# Microcontroller.net
KiCad netlist of a schematic drawn in Altium Designer
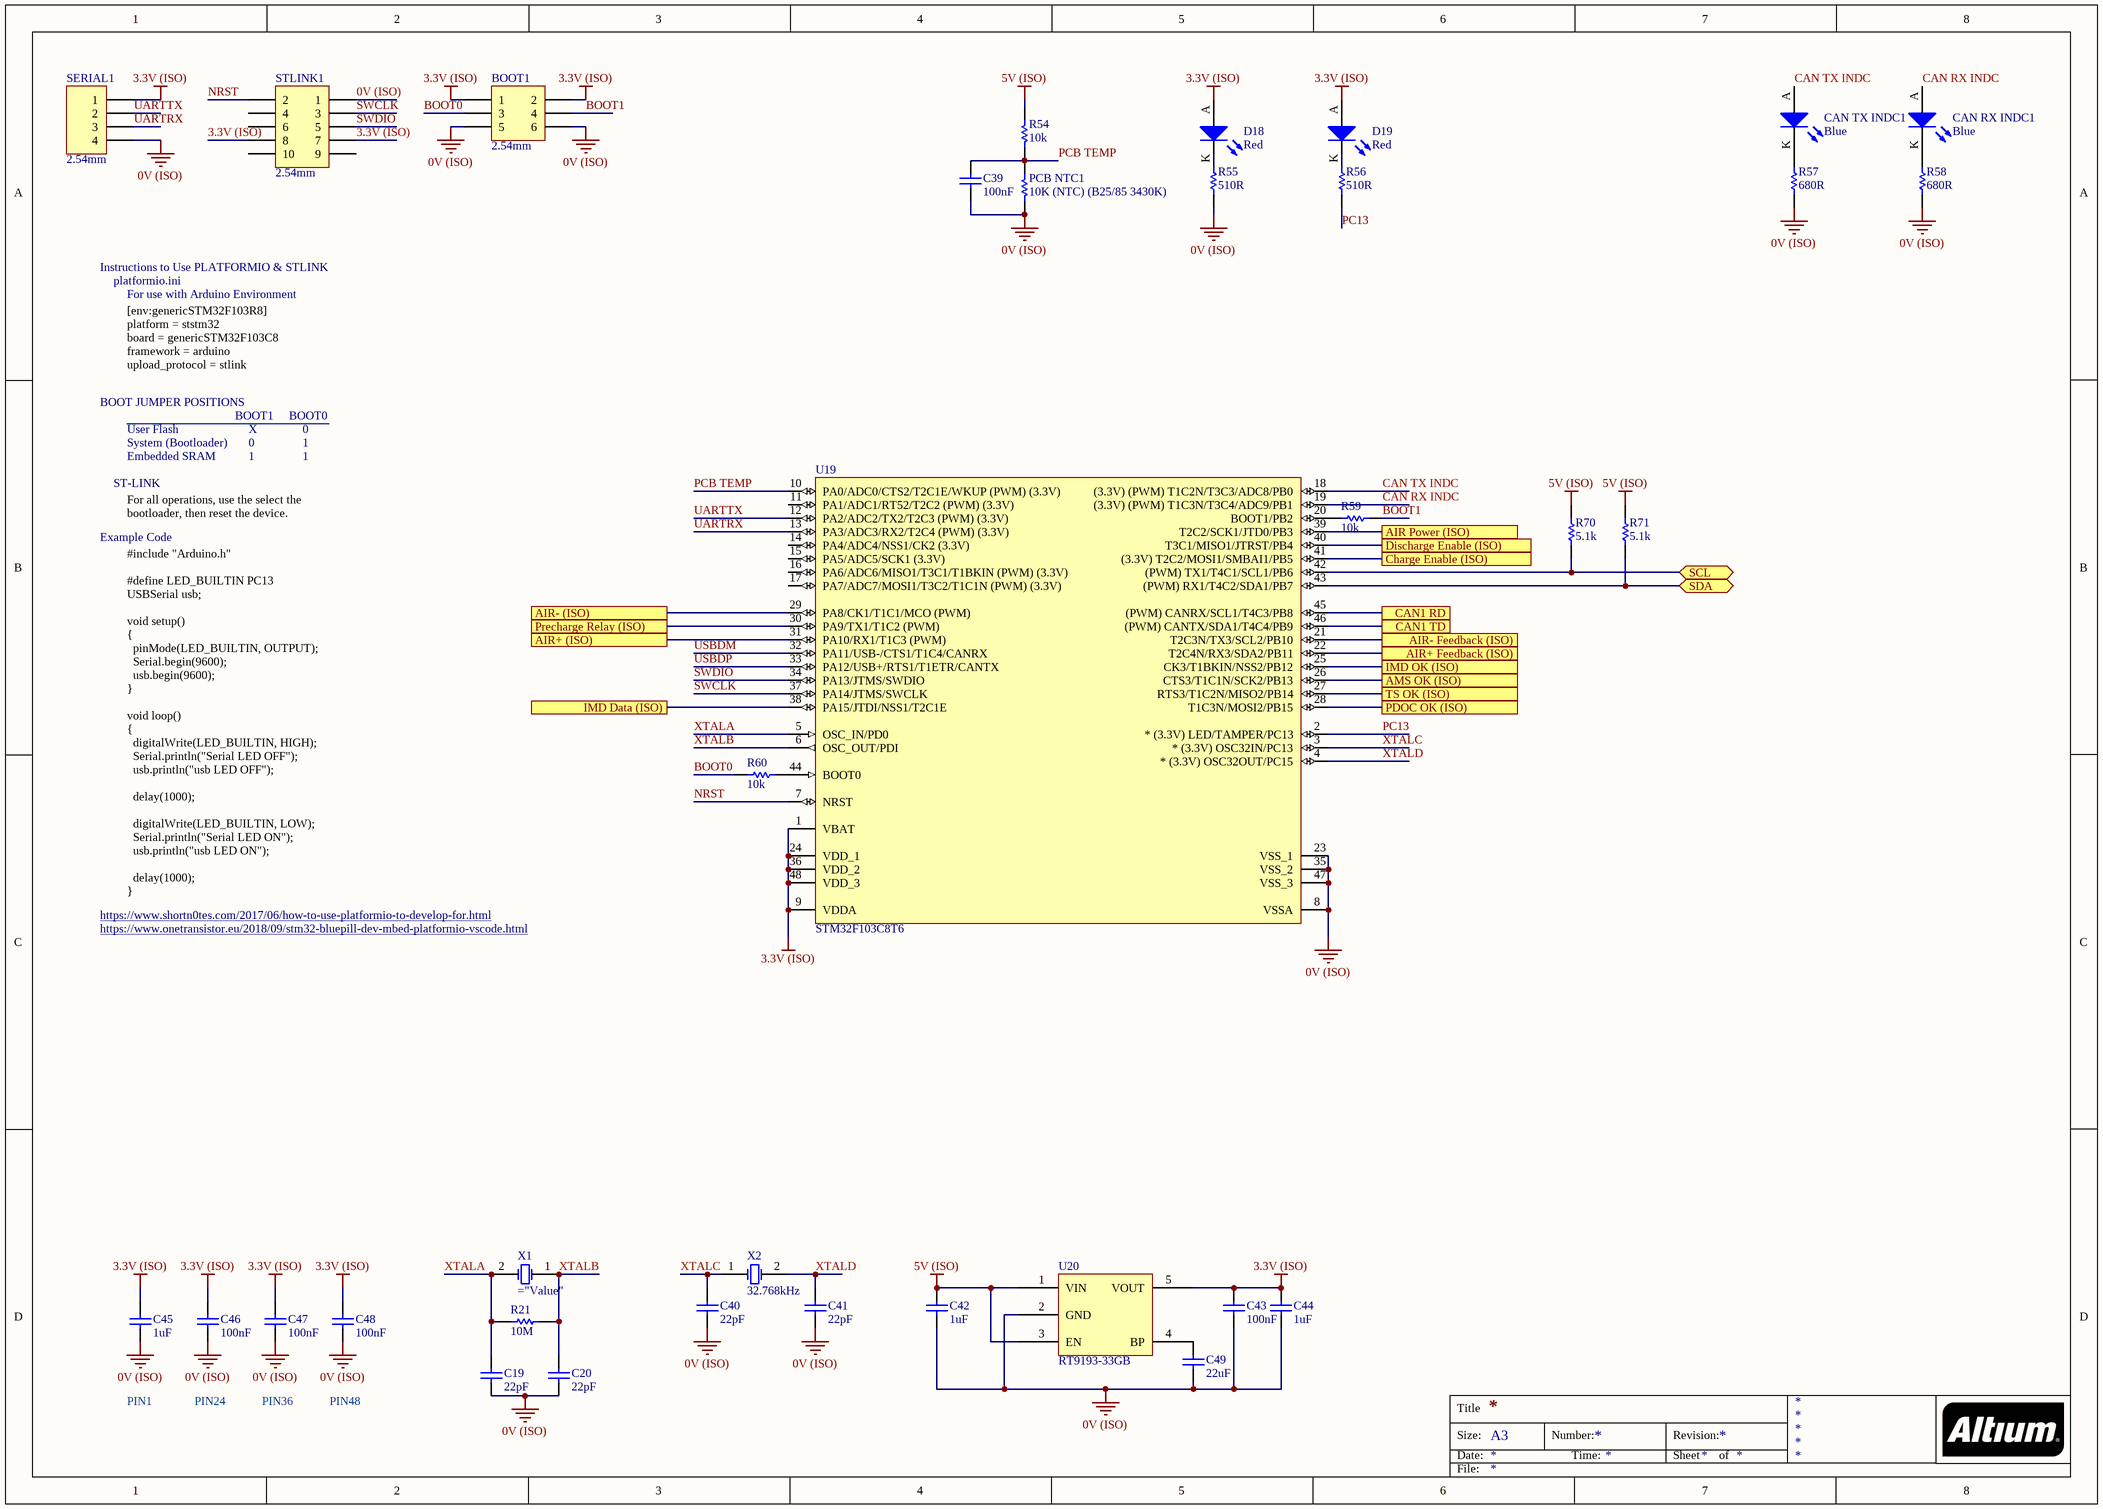
[diagram p0: Microcontroller.SchDoc]

(export (version "E")
  (design (tool "Eeschema 10.0.6"))
  (components
    (comp (ref "BOOT1")
      (value "2.54mm")
      (footprint "TH 2.54mm Header 2x3")
      (fields (field (name "PART NUMBER") "TH 2.54mm Header 2x3") (field (name "CONTACT") "NA"))
      (libsource (lib "ts_20-standard-connectors") (part "Header 2x3"))
    )
    (comp (ref "C19")
      (value "22pF")
      (footprint "0805")
      (fields
        (field (name "PART NUMBER") "GCM21B5C1H220JA37L")
        (field (name "TOLERANCE") "5%")
        (field (name "MANUFACTURER") "muRata")
      )
      (libsource (lib "ts_20-standard-library") (part "Capacitor"))
    )
    (comp (ref "C20")
      (value "22pF")
      (footprint "0805")
      (fields
        (field (name "PART NUMBER") "GCM21B5C1H220JA37L")
        (field (name "TOLERANCE") "5%")
        (field (name "MANUFACTURER") "muRata")
      )
      (libsource (lib "ts_20-standard-library") (part "Capacitor"))
    )
    (comp (ref "C39")
      (value "100nF")
      (footprint "0805")
      (fields
        (field (name "PART NUMBER") "GCM21BR71E104KA37L")
        (field (name "TOLERANCE") "10%")
        (field (name "MANUFACTURER") "muRata")
      )
      (libsource (lib "ts_20-standard-library") (part "Capacitor"))
    )
    (comp (ref "C40")
      (value "22pF")
      (footprint "0805")
      (fields
        (field (name "PART NUMBER") "GCM21B5C1H220JA37L")
        (field (name "TOLERANCE") "5%")
        (field (name "MANUFACTURER") "muRata")
      )
      (libsource (lib "ts_20-standard-library") (part "Capacitor"))
    )
    (comp (ref "C41")
      (value "22pF")
      (footprint "0805")
      (fields
        (field (name "PART NUMBER") "GCM21B5C1H220JA37L")
        (field (name "TOLERANCE") "5%")
        (field (name "MANUFACTURER") "muRata")
      )
      (libsource (lib "ts_20-standard-library") (part "Capacitor"))
    )
    (comp (ref "C42")
      (value "1uF")
      (footprint "0805")
      (fields
        (field (name "PART NUMBER") "GCM21BR71A105KA37L")
        (field (name "TOLERANCE") "10%")
        (field (name "MANUFACTURER") "muRata")
      )
      (libsource (lib "ts_20-standard-library") (part "Capacitor"))
    )
    (comp (ref "C43")
      (value "100nF")
      (footprint "0805")
      (fields
        (field (name "PART NUMBER") "GCM21BR71E104KA37L")
        (field (name "TOLERANCE") "10%")
        (field (name "MANUFACTURER") "muRata")
      )
      (libsource (lib "ts_20-standard-library") (part "Capacitor"))
    )
    (comp (ref "C44")
      (value "1uF")
      (footprint "0805")
      (fields
        (field (name "PART NUMBER") "GCM21BR71A105KA37L")
        (field (name "TOLERANCE") "10%")
        (field (name "MANUFACTURER") "muRata")
      )
      (libsource (lib "ts_20-standard-library") (part "Capacitor"))
    )
    (comp (ref "C45")
      (value "1uF")
      (footprint "0805")
      (fields
        (field (name "PART NUMBER") "GCM21BR71A105KA37L")
        (field (name "TOLERANCE") "10%")
        (field (name "MANUFACTURER") "muRata")
      )
      (libsource (lib "ts_20-standard-library") (part "Capacitor"))
    )
    (comp (ref "C46")
      (value "100nF")
      (footprint "0805")
      (fields
        (field (name "PART NUMBER") "GCM21BR71E104KA37L")
        (field (name "TOLERANCE") "10%")
        (field (name "MANUFACTURER") "muRata")
      )
      (libsource (lib "ts_20-standard-library") (part "Capacitor"))
    )
    (comp (ref "C47")
      (value "100nF")
      (footprint "0805")
      (fields
        (field (name "PART NUMBER") "GCM21BR71E104KA37L")
        (field (name "TOLERANCE") "10%")
        (field (name "MANUFACTURER") "muRata")
      )
      (libsource (lib "ts_20-standard-library") (part "Capacitor"))
    )
    (comp (ref "C48")
      (value "100nF")
      (footprint "0805")
      (fields
        (field (name "PART NUMBER") "GCM21BR71E104KA37L")
        (field (name "TOLERANCE") "10%")
        (field (name "MANUFACTURER") "muRata")
      )
      (libsource (lib "ts_20-standard-library") (part "Capacitor"))
    )
    (comp (ref "C49")
      (value "22uF")
      (footprint "0805")
      (fields
        (field (name "PART NUMBER") "GRM21BR61A226ME51L")
        (field (name "TOLERANCE") "20%")
        (field (name "MANUFACTURER") "muRata")
      )
      (libsource (lib "ts_20-standard-library") (part "Capacitor"))
    )
    (comp (ref "CAN RX INDC1")
      (value "Blue")
      (footprint "0805 LED")
      (description "LED BLUE CLEAR 2012 SMD")
      (fields
        (field (name "PART NUMBER") "SML-MN2BCTT86C")
        (field (name "MANUFACTURER") "ROHM Semiconductor")
      )
      (libsource (lib "ts_20-standard-library") (part "LED"))
    )
    (comp (ref "CAN TX INDC1")
      (value "Blue")
      (footprint "0805 LED")
      (description "LED BLUE CLEAR 2012 SMD")
      (fields
        (field (name "PART NUMBER") "SML-MN2BCTT86C")
        (field (name "MANUFACTURER") "ROHM Semiconductor")
      )
      (libsource (lib "ts_20-standard-library") (part "LED"))
    )
    (comp (ref "D18")
      (value "Red")
      (footprint "0805 LED")
      (description "Red LED Indication - Discrete 1.75V 0805 (2012 Metric)")
      (fields (field (name "MANUFACTURER") "ROHM Semiconductor") (field (name "PART NUMBER") "SML-210LTT86"))
      (libsource (lib "ts_20-standard-library") (part "LED"))
    )
    (comp (ref "D19")
      (value "Red")
      (footprint "0805 LED")
      (description "Red LED Indication - Discrete 1.75V 0805 (2012 Metric)")
      (fields (field (name "MANUFACTURER") "ROHM Semiconductor") (field (name "PART NUMBER") "SML-210LTT86"))
      (libsource (lib "ts_20-standard-library") (part "LED"))
    )
    (comp (ref "PCB NTC1")
      (value "10K (NTC) (B25/85 3430K)")
      (footprint "0805")
      (fields
        (field (name "PART NUMBER") "NTCS0805E3103FLT")
        (field (name "MANUFACTURER") "Vishay Beyschlag")
        (field (name "TOLERANCE") "0.01")
      )
      (libsource (lib "ts_20-standard-library") (part "Resistor"))
    )
    (comp (ref "R21")
      (value "10M")
      (footprint "0805")
      (fields
        (field (name "PART NUMBER") "RC0805FR0710ML")
        (field (name "MANUFACTURER") "YAGEO")
        (field (name "TOLERANCE") "0.01")
      )
      (libsource (lib "ts_20-standard-library") (part "Resistor"))
    )
    (comp (ref "R54")
      (value "10k")
      (footprint "0805")
      (fields
        (field (name "PART NUMBER") "RC0805FR0710KL")
        (field (name "MANUFACTURER") "YAGEO")
        (field (name "TOLERANCE") "0.01")
      )
      (libsource (lib "ts_20-standard-library") (part "Resistor"))
    )
    (comp (ref "R55")
      (value "510R")
      (footprint "0805")
      (fields
        (field (name "MANUFACTURER") "YAGEO")
        (field (name "PART NUMBER") "RC0805FR07510RL")
        (field (name "TOLERANCE") "0.01")
      )
      (libsource (lib "ts_20-standard-library") (part "Resistor"))
    )
    (comp (ref "R56")
      (value "510R")
      (footprint "0805")
      (fields
        (field (name "MANUFACTURER") "YAGEO")
        (field (name "PART NUMBER") "RC0805FR07510RL")
        (field (name "TOLERANCE") "0.01")
      )
      (libsource (lib "ts_20-standard-library") (part "Resistor"))
    )
    (comp (ref "R57")
      (value "680R")
      (footprint "0805")
      (fields
        (field (name "PART NUMBER") "RC0805FR07680RL")
        (field (name "MANUFACTURER") "YAGEO")
        (field (name "TOLERANCE") "0.01")
      )
      (libsource (lib "ts_20-standard-library") (part "Resistor"))
    )
    (comp (ref "R58")
      (value "680R")
      (footprint "0805")
      (fields
        (field (name "PART NUMBER") "RC0805FR07680RL")
        (field (name "MANUFACTURER") "YAGEO")
        (field (name "TOLERANCE") "0.01")
      )
      (libsource (lib "ts_20-standard-library") (part "Resistor"))
    )
    (comp (ref "R59")
      (value "10k")
      (footprint "0805")
      (fields
        (field (name "PART NUMBER") "RC0805FR0710KL")
        (field (name "MANUFACTURER") "YAGEO")
        (field (name "TOLERANCE") "0.01")
      )
      (libsource (lib "ts_20-standard-library") (part "Resistor"))
    )
    (comp (ref "R60")
      (value "10k")
      (footprint "0805")
      (fields
        (field (name "PART NUMBER") "RC0805FR0710KL")
        (field (name "MANUFACTURER") "YAGEO")
        (field (name "TOLERANCE") "0.01")
      )
      (libsource (lib "ts_20-standard-library") (part "Resistor"))
    )
    (comp (ref "R70")
      (value "5.1k")
      (footprint "0805")
      (fields
        (field (name "PART NUMBER") "RC0805FR075K1L")
        (field (name "MANUFACTURER") "YAGEO")
        (field (name "TOLERANCE") "0.01")
      )
      (libsource (lib "ts_20-standard-library") (part "Resistor"))
    )
    (comp (ref "R71")
      (value "5.1k")
      (footprint "0805")
      (fields
        (field (name "PART NUMBER") "RC0805FR075K1L")
        (field (name "MANUFACTURER") "YAGEO")
        (field (name "TOLERANCE") "0.01")
      )
      (libsource (lib "ts_20-standard-library") (part "Resistor"))
    )
    (comp (ref "SERIAL1")
      (value "2.54mm")
      (footprint "TH 2.54mm Header 1x4")
      (fields (field (name "PART NUMBER") "TH 2.54mm Header 1x4") (field (name "CONTACT") "NA"))
      (libsource (lib "ts_20-standard-connectors") (part "Header 1x4"))
    )
    (comp (ref "STLINK1")
      (value "2.54mm")
      (footprint "TH 2.54mm Header 2x5")
      (fields (field (name "PART NUMBER") "TH 2.54mm Header 2x5") (field (name "CONTACT") "NA"))
      (libsource (lib "ts_20-standard-connectors") (part "Header 2x5"))
    )
    (comp (ref "U19")
      (value "STM32F103C8T6")
      (footprint "STM 48-LQFP")
      (description "ARM® Cortex®-M3 STM32F1 Microcontroller IC 32-Bit 72MHz 64KB (64K x 8) FLASH")
      (fields
        (field (name "MANUFACTURER") "STMicroelectronics")
        (field (name "DIGIKEY PART NUMBER") "497-6063-ND")
      )
      (libsource (lib "ts_20-standard-library") (part "STM32F103C8T6"))
    )
    (comp (ref "U20")
      (value "RT9193-33GB")
      (footprint "RICHTEK SOT-23-5")
      (description "IC REG LINEAR 3.3V 300MA SOT23-5")
      (fields (field (name "MANUFACTURER") "Richtek") (field (name "DIGIKEY PART NUMBER") "1028-1014-1-ND"))
      (libsource (lib "ts_20-standard-library") (part "RT9193-33GB"))
    )
    (comp (ref "X1")
      (value "~")
      (footprint "Abracon HC-49/US")
      (fields
        (field (name "PART NUMBER") "ABLS-16.000MHZ-B4-T")
        (field (name "MANUFACTURER") "Abracon LLC")
        (field (name "DIGIKEY PART NUMBER") "535-10226-1-ND")
      )
      (libsource (lib "ts_20-standard-library") (part "Crystal"))
    )
    (comp (ref "X2")
      (value "32.768kHz")
      (footprint "EPSON 2-SMD")
      (fields
        (field (name "PART NUMBER") "FC-135 32.7680KA-A5")
        (field (name "MANUFACTURER") "EPSON")
        (field (name "DIGIKEY PART NUMBER") "SER4103TR-ND")
      )
      (libsource (lib "ts_20-standard-library") (part "Crystal"))
    )
  )
  (nets
    (net (code "1") (name "/AIR Power (ISO)") (class "Default")
      (node (ref "U19") (pin "39") (pinfunction "T2C2/SCK1/JTD0/PB3_39") (pintype "bidirectional"))
    )
    (net (code "2") (name "/AIR+ (ISO)") (class "Default")
      (node (ref "U19") (pin "31") (pinfunction "PA10/RX1/T1C3_(PWM)_31") (pintype "bidirectional"))
    )
    (net (code "3") (name "/AIR+ Feedback (ISO)") (class "Default")
      (node (ref "U19") (pin "22") (pinfunction "T2C4N/RX3/SDA2/PB11_22") (pintype "bidirectional"))
    )
    (net (code "4") (name "/AIR- (ISO)") (class "Default")
      (node (ref "U19") (pin "29") (pinfunction "PA8/CK1/T1C1/MCO_(PWM)_29") (pintype "bidirectional"))
    )
    (net (code "5") (name "/AIR- Feedback (ISO)") (class "Default")
      (node (ref "U19") (pin "21") (pinfunction "T2C3N/TX3/SCL2/PB10_21") (pintype "bidirectional"))
    )
    (net (code "6") (name "/AMS OK (ISO)") (class "Default")
      (node (ref "U19") (pin "26") (pinfunction "CTS3/T1C1N/SCK2/PB13_26") (pintype "bidirectional"))
    )
    (net (code "7") (name "/BOOT0") (class "Default")
      (node (ref "BOOT1") (pin "3") (pinfunction "3_3") (pintype "passive"))
      (node (ref "R60") (pin "1") (pinfunction "1_1") (pintype "passive"))
    )
    (net (code "8") (name "/BOOT1") (class "Default")
      (node (ref "BOOT1") (pin "4") (pinfunction "4_4") (pintype "passive"))
      (node (ref "R59") (pin "2") (pinfunction "2_2") (pintype "passive"))
    )
    (net (code "9") (name "/CAN RX INDC") (class "Default")
      (node (ref "CAN RX INDC1") (pin "A") (pinfunction "A_A") (pintype "passive"))
      (node (ref "U19") (pin "19") (pinfunction "(3.3V)_(PWM)_T1C3N/T3C4/ADC9/PB1_19") (pintype "bidirectional"))
    )
    (net (code "10") (name "/CAN TX INDC") (class "Default")
      (node (ref "CAN TX INDC1") (pin "A") (pinfunction "A_A") (pintype "passive"))
      (node (ref "U19") (pin "18") (pinfunction "(3.3V)_(PWM)_T1C2N/T3C3/ADC8/PB0_18") (pintype "bidirectional"))
    )
    (net (code "11") (name "/CAN1 RD") (class "Default")
      (node (ref "U19") (pin "45") (pinfunction "(PWM)_CANRX/SCL1/T4C3/PB8_45") (pintype "bidirectional"))
    )
    (net (code "12") (name "/CAN1 TD") (class "Default")
      (node (ref "U19") (pin "46") (pinfunction "(PWM)_CANTX/SDA1/T4C4/PB9_46") (pintype "bidirectional"))
    )
    (net (code "13") (name "/Charge Enable (ISO)") (class "Default")
      (node (ref "U19") (pin "41") (pinfunction "(3.3V)_T2C2/MOSI1/SMBAI1/PB5_41") (pintype "bidirectional"))
    )
    (net (code "14") (name "/Discharge Enable (ISO)") (class "Default")
      (node (ref "U19") (pin "40") (pinfunction "T3C1/MISO1/JTRST/PB4_40") (pintype "bidirectional"))
    )
    (net (code "15") (name "/IMD Data (ISO)") (class "Default")
      (node (ref "U19") (pin "38") (pinfunction "PA15/JTDI/NSS1/T2C1E_38") (pintype "bidirectional"))
    )
    (net (code "16") (name "/IMD OK (ISO)") (class "Default")
      (node (ref "U19") (pin "25") (pinfunction "CK3/T1BKIN/NSS2/PB12_25") (pintype "bidirectional"))
    )
    (net (code "17") (name "/NRST") (class "Default")
      (node (ref "STLINK1") (pin "2") (pinfunction "2_2") (pintype "passive"))
      (node (ref "U19") (pin "7") (pinfunction "NRST_7") (pintype "bidirectional"))
    )
    (net (code "18") (name "/PC13") (class "Default")
      (node (ref "R56") (pin "1") (pinfunction "1_1") (pintype "passive"))
      (node (ref "U19") (pin "2") (pinfunction "*_(3.3V)_LED/TAMPER/PC13_2") (pintype "bidirectional"))
    )
    (net (code "19") (name "/PCB TEMP") (class "Default")
      (node (ref "C39") (pin "2") (pinfunction "2_2") (pintype "passive"))
      (node (ref "PCB NTC1") (pin "2") (pinfunction "2_2") (pintype "passive"))
      (node (ref "R54") (pin "1") (pinfunction "1_1") (pintype "passive"))
      (node (ref "U19") (pin "10") (pinfunction "PA0/ADC0/CTS2/T2C1E/WKUP_(PWM)_(3.3V)_10") (pintype "bidirectional"))
    )
    (net (code "20") (name "/PDOC OK (ISO)") (class "Default")
      (node (ref "U19") (pin "28") (pinfunction "T1C3N/MOSI2/PB15_28") (pintype "bidirectional"))
    )
    (net (code "21") (name "/Precharge Relay (ISO)") (class "Default")
      (node (ref "U19") (pin "30") (pinfunction "PA9/TX1/T1C2_(PWM)_30") (pintype "bidirectional"))
    )
    (net (code "22") (name "/SCL") (class "Default")
      (node (ref "R70") (pin "1") (pinfunction "1_1") (pintype "passive"))
      (node (ref "U19") (pin "42") (pinfunction "(PWM)_TX1/T4C1/SCL1/PB6_42") (pintype "bidirectional"))
    )
    (net (code "23") (name "/SDA") (class "Default")
      (node (ref "R71") (pin "1") (pinfunction "1_1") (pintype "passive"))
      (node (ref "U19") (pin "43") (pinfunction "(PWM)_RX1/T4C2/SDA1/PB7_43") (pintype "bidirectional"))
    )
    (net (code "24") (name "/SWCLK") (class "Default")
      (node (ref "STLINK1") (pin "3") (pinfunction "3_3") (pintype "passive"))
      (node (ref "U19") (pin "37") (pinfunction "PA14/JTMS/SWCLK_37") (pintype "bidirectional"))
    )
    (net (code "25") (name "/SWDIO") (class "Default")
      (node (ref "STLINK1") (pin "5") (pinfunction "5_5") (pintype "passive"))
      (node (ref "U19") (pin "34") (pinfunction "PA13/JTMS/SWDIO_34") (pintype "bidirectional"))
    )
    (net (code "26") (name "/TS OK (ISO)") (class "Default")
      (node (ref "U19") (pin "27") (pinfunction "RTS3/T1C2N/MISO2/PB14_27") (pintype "bidirectional"))
    )
    (net (code "27") (name "/UARTRX") (class "Default")
      (node (ref "SERIAL1") (pin "3") (pinfunction "3_3") (pintype "passive"))
      (node (ref "U19") (pin "13") (pinfunction "PA3/ADC3/RX2/T2C4_(PWM)_(3.3V)_13") (pintype "bidirectional"))
    )
    (net (code "28") (name "/UARTTX") (class "Default")
      (node (ref "SERIAL1") (pin "2") (pinfunction "2_2") (pintype "passive"))
      (node (ref "U19") (pin "12") (pinfunction "PA2/ADC2/TX2/T2C3_(PWM)_(3.3V)_12") (pintype "bidirectional"))
    )
    (net (code "29") (name "/USBDM") (class "Default")
      (node (ref "U19") (pin "32") (pinfunction "PA11/USB-/CTS1/T1C4/CANRX_32") (pintype "bidirectional"))
    )
    (net (code "30") (name "/USBDP") (class "Default")
      (node (ref "U19") (pin "33") (pinfunction "PA12/USB+/RTS1/T1ETR/CANTX_33") (pintype "bidirectional"))
    )
    (net (code "31") (name "/XTALA") (class "Default")
      (node (ref "C19") (pin "2") (pinfunction "2_2") (pintype "passive"))
      (node (ref "R21") (pin "2") (pinfunction "2_2") (pintype "passive"))
      (node (ref "U19") (pin "5") (pinfunction "OSC_IN/PD0_5") (pintype "input"))
      (node (ref "X1") (pin "2") (pinfunction "OSC2_2") (pintype "passive"))
    )
    (net (code "32") (name "/XTALB") (class "Default")
      (node (ref "C20") (pin "2") (pinfunction "2_2") (pintype "passive"))
      (node (ref "R21") (pin "1") (pinfunction "1_1") (pintype "passive"))
      (node (ref "U19") (pin "6") (pinfunction "OSC_OUT/PDI_6") (pintype "output"))
      (node (ref "X1") (pin "1") (pinfunction "OSC1_1") (pintype "passive"))
    )
    (net (code "33") (name "/XTALC") (class "Default")
      (node (ref "C40") (pin "2") (pinfunction "2_2") (pintype "passive"))
      (node (ref "U19") (pin "3") (pinfunction "*_(3.3V)_OSC32IN/PC13_3") (pintype "bidirectional"))
      (node (ref "X2") (pin "1") (pinfunction "OSC1_1") (pintype "passive"))
    )
    (net (code "34") (name "/XTALD") (class "Default")
      (node (ref "C41") (pin "2") (pinfunction "2_2") (pintype "passive"))
      (node (ref "U19") (pin "4") (pinfunction "*_(3.3V)_OSC32OUT/PC15_4") (pintype "bidirectional"))
      (node (ref "X2") (pin "2") (pinfunction "OSC2_2") (pintype "passive"))
    )
    (net (code "35") (name "0V (ISO)") (class "Default")
      (node (ref "BOOT1") (pin "5") (pinfunction "5_5") (pintype "passive"))
      (node (ref "BOOT1") (pin "6") (pinfunction "6_6") (pintype "passive"))
      (node (ref "C19") (pin "1") (pinfunction "1_1") (pintype "passive"))
      (node (ref "C20") (pin "1") (pinfunction "1_1") (pintype "passive"))
      (node (ref "C39") (pin "1") (pinfunction "1_1") (pintype "passive"))
      (node (ref "C40") (pin "1") (pinfunction "1_1") (pintype "passive"))
      (node (ref "C41") (pin "1") (pinfunction "1_1") (pintype "passive"))
      (node (ref "C42") (pin "1") (pinfunction "1_1") (pintype "passive"))
      (node (ref "C43") (pin "1") (pinfunction "1_1") (pintype "passive"))
      (node (ref "C44") (pin "1") (pinfunction "1_1") (pintype "passive"))
      (node (ref "C45") (pin "1") (pinfunction "1_1") (pintype "passive"))
      (node (ref "C46") (pin "1") (pinfunction "1_1") (pintype "passive"))
      (node (ref "C47") (pin "1") (pinfunction "1_1") (pintype "passive"))
      (node (ref "C48") (pin "1") (pinfunction "1_1") (pintype "passive"))
      (node (ref "C49") (pin "1") (pinfunction "1_1") (pintype "passive"))
      (node (ref "PCB NTC1") (pin "1") (pinfunction "1_1") (pintype "passive"))
      (node (ref "R55") (pin "1") (pinfunction "1_1") (pintype "passive"))
      (node (ref "R57") (pin "1") (pinfunction "1_1") (pintype "passive"))
      (node (ref "R58") (pin "1") (pinfunction "1_1") (pintype "passive"))
      (node (ref "SERIAL1") (pin "4") (pinfunction "4_4") (pintype "passive"))
      (node (ref "STLINK1") (pin "1") (pinfunction "1_1") (pintype "passive"))
      (node (ref "U19") (pin "23") (pinfunction "VSS_1_23") (pintype "power_in"))
      (node (ref "U19") (pin "35") (pinfunction "VSS_2_35") (pintype "power_in"))
      (node (ref "U19") (pin "47") (pinfunction "VSS_3_47") (pintype "power_in"))
      (node (ref "U19") (pin "8") (pinfunction "VSSA_8") (pintype "power_in"))
      (node (ref "U20") (pin "2") (pinfunction "GND_2") (pintype "passive"))
    )
    (net (code "36") (name "3.3V (ISO)") (class "Default")
      (node (ref "BOOT1") (pin "1") (pinfunction "1_1") (pintype "passive"))
      (node (ref "BOOT1") (pin "2") (pinfunction "2_2") (pintype "passive"))
      (node (ref "C43") (pin "2") (pinfunction "2_2") (pintype "passive"))
      (node (ref "C44") (pin "2") (pinfunction "2_2") (pintype "passive"))
      (node (ref "C45") (pin "2") (pinfunction "2_2") (pintype "passive"))
      (node (ref "C46") (pin "2") (pinfunction "2_2") (pintype "passive"))
      (node (ref "C47") (pin "2") (pinfunction "2_2") (pintype "passive"))
      (node (ref "C48") (pin "2") (pinfunction "2_2") (pintype "passive"))
      (node (ref "D18") (pin "A") (pinfunction "A_A") (pintype "passive"))
      (node (ref "D19") (pin "A") (pinfunction "A_A") (pintype "passive"))
      (node (ref "SERIAL1") (pin "1") (pinfunction "1_1") (pintype "passive"))
      (node (ref "STLINK1") (pin "7") (pinfunction "7_7") (pintype "passive"))
      (node (ref "STLINK1") (pin "8") (pinfunction "8_8") (pintype "passive"))
      (node (ref "U19") (pin "1") (pinfunction "VBAT_1") (pintype "power_in"))
      (node (ref "U19") (pin "24") (pinfunction "VDD_1_24") (pintype "power_in"))
      (node (ref "U19") (pin "36") (pinfunction "VDD_2_36") (pintype "power_in"))
      (node (ref "U19") (pin "48") (pinfunction "VDD_3_48") (pintype "power_in"))
      (node (ref "U19") (pin "9") (pinfunction "VDDA_9") (pintype "power_in"))
      (node (ref "U20") (pin "5") (pinfunction "VOUT_5") (pintype "passive"))
    )
    (net (code "37") (name "5V (ISO)") (class "Default")
      (node (ref "C42") (pin "2") (pinfunction "2_2") (pintype "passive"))
      (node (ref "R54") (pin "2") (pinfunction "2_2") (pintype "passive"))
      (node (ref "R70") (pin "2") (pinfunction "2_2") (pintype "passive"))
      (node (ref "R71") (pin "2") (pinfunction "2_2") (pintype "passive"))
      (node (ref "U20") (pin "1") (pinfunction "VIN_1") (pintype "passive"))
      (node (ref "U20") (pin "3") (pinfunction "EN_3") (pintype "passive"))
    )
    (net (code "38") (name "Net-(CAN RX INDC1-PadK)") (class "Default")
      (node (ref "CAN RX INDC1") (pin "K") (pinfunction "K_K") (pintype "passive"))
      (node (ref "R58") (pin "2") (pinfunction "2_2") (pintype "passive"))
    )
    (net (code "39") (name "Net-(CAN TX INDC1-PadK)") (class "Default")
      (node (ref "CAN TX INDC1") (pin "K") (pinfunction "K_K") (pintype "passive"))
      (node (ref "R57") (pin "2") (pinfunction "2_2") (pintype "passive"))
    )
    (net (code "40") (name "Net-(D18-PadK)") (class "Default")
      (node (ref "D18") (pin "K") (pinfunction "K_K") (pintype "passive"))
      (node (ref "R55") (pin "2") (pinfunction "2_2") (pintype "passive"))
    )
    (net (code "41") (name "Net-(D19-PadK)") (class "Default")
      (node (ref "D19") (pin "K") (pinfunction "K_K") (pintype "passive"))
      (node (ref "R56") (pin "2") (pinfunction "2_2") (pintype "passive"))
    )
    (net (code "42") (name "Net-(U19-BOOT0)") (class "Default")
      (node (ref "R60") (pin "2") (pinfunction "2_2") (pintype "passive"))
      (node (ref "U19") (pin "44") (pinfunction "BOOT0_44") (pintype "input"))
    )
    (net (code "43") (name "Net-(U19-BOOT1{slash}PB2)") (class "Default")
      (node (ref "R59") (pin "1") (pinfunction "1_1") (pintype "passive"))
      (node (ref "U19") (pin "20") (pinfunction "BOOT1/PB2_20") (pintype "bidirectional"))
    )
    (net (code "44") (name "Net-(U20-BP)") (class "Default")
      (node (ref "C49") (pin "2") (pinfunction "2_2") (pintype "passive"))
      (node (ref "U20") (pin "4") (pinfunction "BP_4") (pintype "passive"))
    )
    (net (code "45") (name "unconnected-(STLINK1-Pad4)") (class "Default")
      (node (ref "STLINK1") (pin "4") (pinfunction "4_4") (pintype "passive"))
    )
    (net (code "46") (name "unconnected-(STLINK1-Pad6)") (class "Default")
      (node (ref "STLINK1") (pin "6") (pinfunction "6_6") (pintype "passive"))
    )
    (net (code "47") (name "unconnected-(STLINK1-Pad9)") (class "Default")
      (node (ref "STLINK1") (pin "9") (pinfunction "9_9") (pintype "passive"))
    )
    (net (code "48") (name "unconnected-(STLINK1-Pad10)") (class "Default")
      (node (ref "STLINK1") (pin "10") (pinfunction "10_10") (pintype "passive"))
    )
    (net (code "49") (name "unconnected-(U19-PA1{slash}ADC1{slash}RT52{slash}T2C2_(PWM)_(3.3V)-Pad11)") (class "Default")
      (node (ref "U19") (pin "11") (pinfunction "PA1/ADC1/RT52/T2C2_(PWM)_(3.3V)_11") (pintype "bidirectional"))
    )
    (net (code "50") (name "unconnected-(U19-PA4{slash}ADC4{slash}NSS1{slash}CK2_(3.3V)-Pad14)") (class "Default")
      (node (ref "U19") (pin "14") (pinfunction "PA4/ADC4/NSS1/CK2_(3.3V)_14") (pintype "bidirectional"))
    )
    (net (code "51") (name "unconnected-(U19-PA5{slash}ADC5{slash}SCK1_(3.3V)-Pad15)") (class "Default")
      (node (ref "U19") (pin "15") (pinfunction "PA5/ADC5/SCK1_(3.3V)_15") (pintype "bidirectional"))
    )
    (net (code "52") (name "unconnected-(U19-PA6{slash}ADC6{slash}MISO1{slash}T3C1{slash}T1BKIN_(PWM)_(3.3V)-Pad16)") (class "Default")
      (node (ref "U19") (pin "16") (pinfunction "PA6/ADC6/MISO1/T3C1/T1BKIN_(PWM)_(3.3V)_16") (pintype "bidirectional"))
    )
    (net (code "53") (name "unconnected-(U19-PA7{slash}ADC7{slash}MOSI1{slash}T3C2{slash}T1C1N_(PWM)_(3.3V)-Pad17)") (class "Default")
      (node (ref "U19") (pin "17") (pinfunction "PA7/ADC7/MOSI1/T3C2/T1C1N_(PWM)_(3.3V)_17") (pintype "bidirectional"))
    )
  )
)
